# 2.net
KiCad netlist of a schematic drawn in Altium Designer
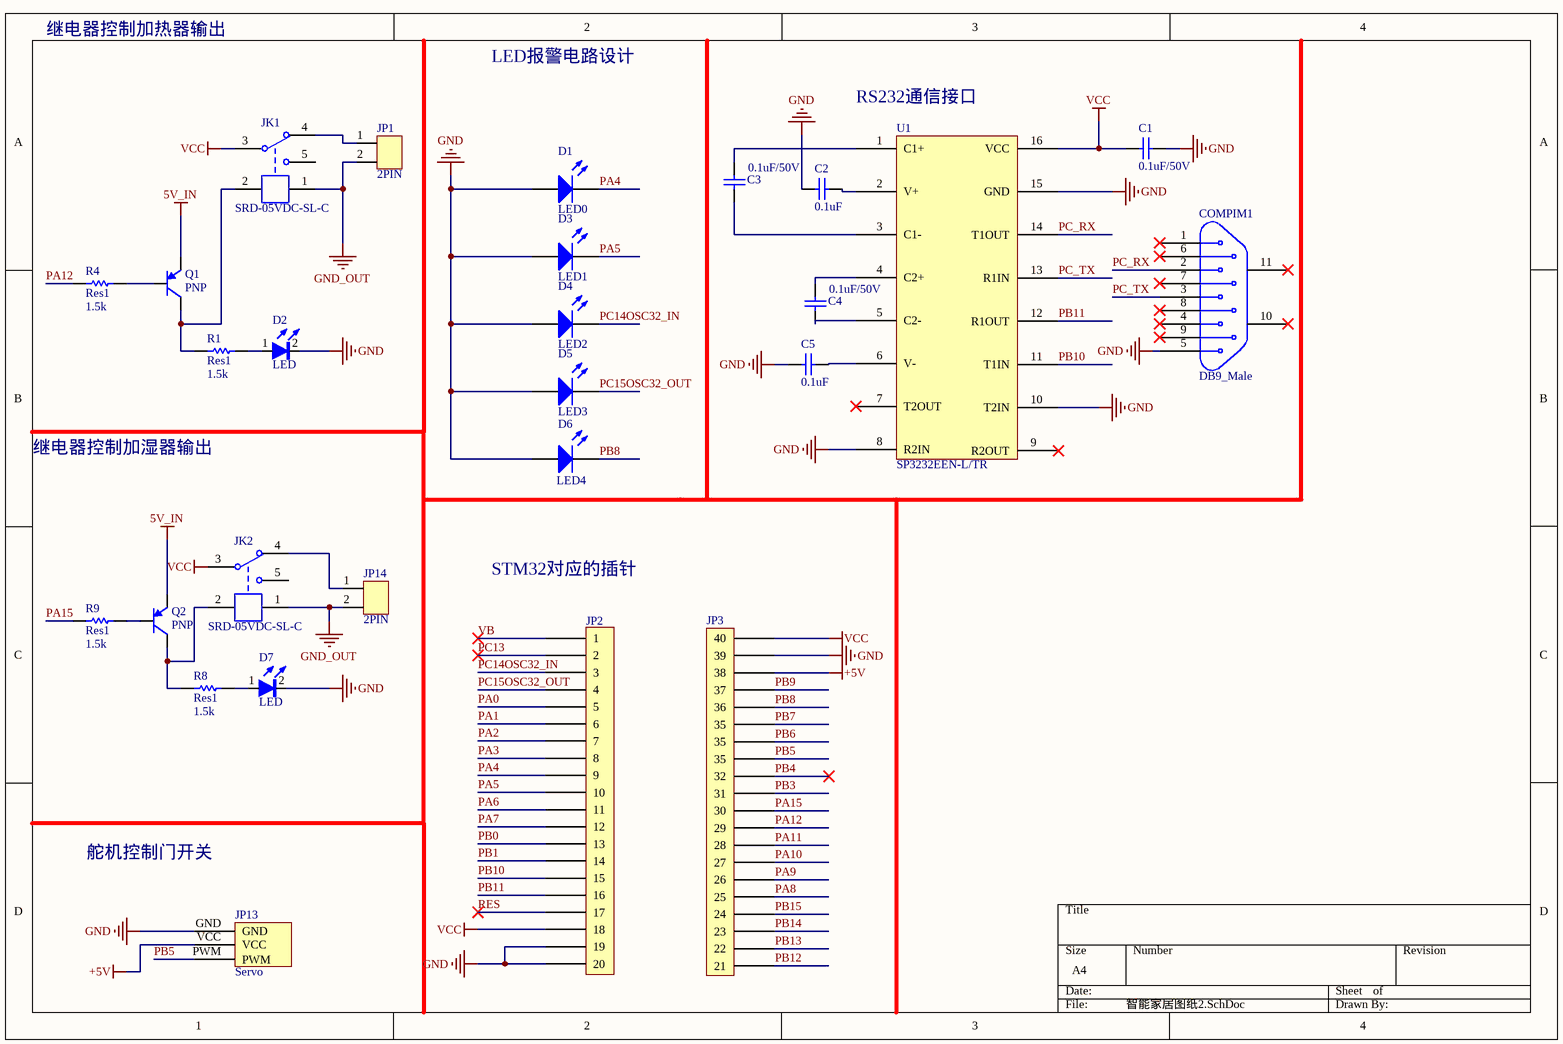
[diagram p0: 智能家居图纸2.SchDoc]

(export (version "E")
  (design (tool "Eeschema 10.0.6"))
  (components
    (comp (ref "C1")
      (value "0.1uF/50V")
      (footprint "C0603")
      (description "Capacitor")
      (fields (field (name "Comment") "Cap") (field (name "PUBLISHER") "Altium Limited"))
      (libsource (lib "Miscellaneous Devices") (part "Cap"))
    )
    (comp (ref "C2")
      (value "0.1uF")
      (footprint "C0603")
      (description "Capacitor")
      (fields (field (name "Comment") "Cap") (field (name "PUBLISHER") "Altium Limited"))
      (libsource (lib "Miscellaneous Devices") (part "Cap"))
    )
    (comp (ref "C3")
      (value "0.1uF/50V")
      (footprint "C0603")
      (description "Capacitor")
      (fields (field (name "Comment") "Cap") (field (name "PUBLISHER") "Altium Limited"))
      (libsource (lib "Miscellaneous Devices") (part "Cap"))
    )
    (comp (ref "C4")
      (value "0.1uF/50V")
      (footprint "C0603")
      (description "Capacitor")
      (fields (field (name "Comment") "Cap") (field (name "PUBLISHER") "Altium Limited"))
      (libsource (lib "Miscellaneous Devices") (part "Cap"))
    )
    (comp (ref "C5")
      (value "0.1uF")
      (footprint "C0603")
      (description "Capacitor")
      (fields (field (name "Comment") "Cap") (field (name "PUBLISHER") "Altium Limited"))
      (libsource (lib "Miscellaneous Devices") (part "Cap"))
    )
    (comp (ref "COMPIM1")
      (value "DB9_Male")
      (footprint "DB9Male")
      (description "9针串口线  RS232")
      (libsource (lib "智能家居") (part "DB9_Male"))
    )
    (comp (ref "D1")
      (value "LED0")
      (footprint "LED-Green")
      (description "Typical INFRARED GaAs LED")
      (fields (field (name "PUBLISHER") "Altium Limited"))
      (libsource (lib "Miscellaneous Devices") (part "LED0"))
    )
    (comp (ref "D2")
      (value "LED")
      (footprint "LED-Green")
      (description "发光二极管")
      (libsource (lib "智能家居") (part "LED"))
    )
    (comp (ref "D3")
      (value "LED1")
      (footprint "LED-Red")
      (description "Typical RED GaAs LED")
      (fields (field (name "PUBLISHER") "Altium Limited"))
      (libsource (lib "Miscellaneous Devices") (part "LED1"))
    )
    (comp (ref "D4")
      (value "LED2")
      (footprint "LED-White")
      (description "Typical RED, GREEN, YELLOW, AMBER GaAs LED")
      (fields (field (name "PUBLISHER") "Altium Limited"))
      (libsource (lib "Miscellaneous Devices") (part "LED2"))
    )
    (comp (ref "D5")
      (value "LED3")
      (footprint "LED-yellow")
      (description "Typical BLUE SiC LED")
      (fields (field (name "PUBLISHER") "Altium Limited"))
      (libsource (lib "Miscellaneous Devices") (part "LED3"))
    )
    (comp (ref "D6")
      (value "LED4")
      (footprint "LED-yellow")
      (description "发光二极管")
      (libsource (lib "0.3 - LED发光二极管") (part "LED"))
    )
    (comp (ref "D7")
      (value "LED")
      (footprint "LED-Red")
      (description "发光二极管")
      (libsource (lib "智能家居") (part "LED"))
    )
    (comp (ref "JK1")
      (value "SRD-05VDC-SL-C")
      (footprint "SRD-C_B")
      (description "5V一组转换")
      (fields (field (name "版权归属") "封装库来自淘宝卖家 ID：黄晶宝石"))
      (libsource (lib "1.5 - 继电器") (part "SRD-05VDC-SL-C"))
    )
    (comp (ref "JK2")
      (value "SRD-05VDC-SL-C")
      (footprint "SRD-C_B")
      (description "5V一组转换")
      (fields (field (name "版权归属") "封装库来自淘宝卖家 ID：黄晶宝石"))
      (libsource (lib "1.5 - 继电器") (part "SRD-05VDC-SL-C"))
    )
    (comp (ref "JP1")
      (value "2PIN")
      (footprint "2PIN")
      (description "插针")
      (libsource (lib "智能家居") (part "JP"))
    )
    (comp (ref "JP2")
      (value "JP3")
      (footprint "HDR1X20")
      (description "STM32插针第一列")
      (libsource (lib "智能家居") (part "JP3"))
    )
    (comp (ref "JP3")
      (value "JP4")
      (footprint "HDR1X20-2")
      (description "STM32插针第二列")
      (libsource (lib "智能家居") (part "JP4"))
    )
    (comp (ref "JP13")
      (value "Servo")
      (footprint "HDR1X3-5")
      (description "舵机")
      (libsource (lib "智能家居") (part "Servo"))
    )
    (comp (ref "JP14")
      (value "2PIN")
      (footprint "2PIN")
      (description "插针")
      (libsource (lib "智能家居") (part "JP"))
    )
    (comp (ref "Q1")
      (value "PNP")
      (footprint "PNP")
      (description "互补功率-PNP型")
      (fields (field (name "版权归属") "封装库来自淘宝 ID：黄晶宝石"))
      (libsource (lib "0.4 - 三极管") (part "45H11"))
    )
    (comp (ref "Q2")
      (value "PNP")
      (footprint "PNP")
      (description "互补功率-PNP型")
      (fields (field (name "版权归属") "封装库来自淘宝 ID：黄晶宝石"))
      (libsource (lib "0.4 - 三极管") (part "45H11"))
    )
    (comp (ref "R1")
      (value "Res1")
      (footprint "R200")
      (description "Resistor")
      (fields (field (name "ALTIUM_VALUE") "1.5k") (field (name "PUBLISHER") "Altium Limited"))
      (libsource (lib "Miscellaneous Devices") (part "Res1"))
    )
    (comp (ref "R4")
      (value "Res1")
      (footprint "R200")
      (description "Resistor")
      (fields (field (name "ALTIUM_VALUE") "1.5k") (field (name "PUBLISHER") "Altium Limited"))
      (libsource (lib "Miscellaneous Devices") (part "Res1"))
    )
    (comp (ref "R8")
      (value "Res1")
      (footprint "R200")
      (description "Resistor")
      (fields (field (name "ALTIUM_VALUE") "1.5k") (field (name "PUBLISHER") "Altium Limited"))
      (libsource (lib "Miscellaneous Devices") (part "Res1"))
    )
    (comp (ref "R9")
      (value "Res1")
      (footprint "R200")
      (description "Resistor")
      (fields (field (name "ALTIUM_VALUE") "1.5k") (field (name "PUBLISHER") "Altium Limited"))
      (libsource (lib "Miscellaneous Devices") (part "Res1"))
    )
    (comp (ref "U1")
      (value "SP3232EEN-L/TR")
      (footprint "SOP127P600X175-16N")
      (description "RS-232接口集成电路")
      (libsource (lib "智能家居") (part "SP3232EEN-L/TR"))
    )
  )
  (nets
    (net (code "1") (name "+5V") (class "Default")
      (node (ref "JP13") (pin "VCC") (pinfunction "VCC_VCC") (pintype "passive"))
      (node (ref "JP3") (pin "38") (pinfunction "38_38") (pintype "passive"))
    )
    (net (code "2") (name "/PA0") (class "Default")
      (node (ref "JP2") (pin "5") (pinfunction "5_5") (pintype "passive"))
    )
    (net (code "3") (name "/PA1") (class "Default")
      (node (ref "JP2") (pin "6") (pinfunction "6_6") (pintype "passive"))
    )
    (net (code "4") (name "/PA2") (class "Default")
      (node (ref "JP2") (pin "7") (pinfunction "7_7") (pintype "passive"))
    )
    (net (code "5") (name "/PA3") (class "Default")
      (node (ref "JP2") (pin "8") (pinfunction "8_8") (pintype "passive"))
    )
    (net (code "6") (name "/PA4") (class "Default")
      (node (ref "D1") (pin "2") (pinfunction "K_2") (pintype "passive"))
      (node (ref "JP2") (pin "9") (pinfunction "9_9") (pintype "passive"))
    )
    (net (code "7") (name "/PA5") (class "Default")
      (node (ref "D3") (pin "2") (pinfunction "K_2") (pintype "passive"))
      (node (ref "JP2") (pin "10") (pinfunction "10_10") (pintype "passive"))
    )
    (net (code "8") (name "/PA6") (class "Default")
      (node (ref "JP2") (pin "11") (pinfunction "11_11") (pintype "passive"))
    )
    (net (code "9") (name "/PA7") (class "Default")
      (node (ref "JP2") (pin "12") (pinfunction "12_12") (pintype "passive"))
    )
    (net (code "10") (name "/PA8") (class "Default")
      (node (ref "JP3") (pin "25") (pinfunction "25_25") (pintype "passive"))
    )
    (net (code "11") (name "/PA9") (class "Default")
      (node (ref "JP3") (pin "26") (pinfunction "26_26") (pintype "passive"))
    )
    (net (code "12") (name "/PA10") (class "Default")
      (node (ref "JP3") (pin "27") (pinfunction "27_27") (pintype "passive"))
    )
    (net (code "13") (name "/PA11") (class "Default")
      (node (ref "JP3") (pin "28") (pinfunction "28_28") (pintype "passive"))
    )
    (net (code "14") (name "/PA12") (class "Default")
      (node (ref "JP3") (pin "29") (pinfunction "29_29") (pintype "passive"))
      (node (ref "R4") (pin "2") (pinfunction "2_2") (pintype "passive"))
    )
    (net (code "15") (name "/PA15") (class "Default")
      (node (ref "JP3") (pin "30") (pinfunction "30_30") (pintype "passive"))
      (node (ref "R9") (pin "2") (pinfunction "2_2") (pintype "passive"))
    )
    (net (code "16") (name "/PB0") (class "Default")
      (node (ref "JP2") (pin "13") (pinfunction "13_13") (pintype "passive"))
    )
    (net (code "17") (name "/PB1") (class "Default")
      (node (ref "JP2") (pin "14") (pinfunction "14_14") (pintype "passive"))
    )
    (net (code "18") (name "/PB3") (class "Default")
      (node (ref "JP3") (pin "31") (pinfunction "31_31") (pintype "passive"))
    )
    (net (code "19") (name "/PB4") (class "Default")
      (node (ref "JP3") (pin "32") (pinfunction "32_32") (pintype "passive+no_connect"))
    )
    (net (code "20") (name "/PB5") (class "Default")
      (node (ref "JP13") (pin "PWM") (pinfunction "PWM_PWM") (pintype "passive"))
      (node (ref "JP3") (pin "33") (pinfunction "35_33") (pintype "passive"))
    )
    (net (code "21") (name "/PB6") (class "Default")
      (node (ref "JP3") (pin "34") (pinfunction "35_34") (pintype "passive"))
    )
    (net (code "22") (name "/PB7") (class "Default")
      (node (ref "JP3") (pin "35") (pinfunction "35_35") (pintype "passive"))
    )
    (net (code "23") (name "/PB8") (class "Default")
      (node (ref "D6") (pin "2") (pinfunction "K_2") (pintype "passive"))
      (node (ref "JP3") (pin "36") (pinfunction "36_36") (pintype "passive"))
    )
    (net (code "24") (name "/PB9") (class "Default")
      (node (ref "JP3") (pin "37") (pinfunction "37_37") (pintype "passive"))
    )
    (net (code "25") (name "/PB10") (class "Default")
      (node (ref "JP2") (pin "15") (pinfunction "15_15") (pintype "passive"))
      (node (ref "U1") (pin "11") (pinfunction "T1IN_11") (pintype "passive"))
    )
    (net (code "26") (name "/PB11") (class "Default")
      (node (ref "JP2") (pin "16") (pinfunction "16_16") (pintype "passive"))
      (node (ref "U1") (pin "12") (pinfunction "R1OUT_12") (pintype "passive"))
    )
    (net (code "27") (name "/PB12") (class "Default")
      (node (ref "JP3") (pin "21") (pinfunction "21_21") (pintype "passive"))
    )
    (net (code "28") (name "/PB13") (class "Default")
      (node (ref "JP3") (pin "22") (pinfunction "22_22") (pintype "passive"))
    )
    (net (code "29") (name "/PB14") (class "Default")
      (node (ref "JP3") (pin "23") (pinfunction "23_23") (pintype "passive"))
    )
    (net (code "30") (name "/PB15") (class "Default")
      (node (ref "JP3") (pin "24") (pinfunction "24_24") (pintype "passive"))
    )
    (net (code "31") (name "/PC13") (class "Default")
      (node (ref "JP2") (pin "2") (pinfunction "2_2") (pintype "passive+no_connect"))
    )
    (net (code "32") (name "/PC14OSC32_IN") (class "Default")
      (node (ref "D4") (pin "2") (pinfunction "K_2") (pintype "passive"))
      (node (ref "JP2") (pin "3") (pinfunction "3_3") (pintype "passive"))
    )
    (net (code "33") (name "/PC15OSC32_OUT") (class "Default")
      (node (ref "D5") (pin "2") (pinfunction "K_2") (pintype "passive"))
      (node (ref "JP2") (pin "4") (pinfunction "4_4") (pintype "passive"))
    )
    (net (code "34") (name "/PC_RX") (class "Default")
      (node (ref "COMPIM1") (pin "2") (pintype "passive"))
      (node (ref "U1") (pin "14") (pinfunction "T1OUT_14") (pintype "passive"))
    )
    (net (code "35") (name "/PC_TX") (class "Default")
      (node (ref "COMPIM1") (pin "3") (pintype "passive"))
      (node (ref "U1") (pin "13") (pinfunction "R1IN_13") (pintype "passive"))
    )
    (net (code "36") (name "/RES") (class "Default")
      (node (ref "JP2") (pin "17") (pinfunction "17_17") (pintype "passive+no_connect"))
    )
    (net (code "37") (name "/VB") (class "Default")
      (node (ref "JP2") (pin "1") (pinfunction "1_1") (pintype "passive+no_connect"))
    )
    (net (code "38") (name "5V_IN") (class "Default")
      (node (ref "Q1") (pin "3") (pinfunction "E_3") (pintype "passive"))
      (node (ref "Q2") (pin "3") (pinfunction "E_3") (pintype "passive"))
    )
    (net (code "39") (name "GND") (class "Default")
      (node (ref "C1") (pin "1") (pinfunction "1_1") (pintype "passive"))
      (node (ref "C2") (pin "1") (pinfunction "1_1") (pintype "passive"))
      (node (ref "C5") (pin "1") (pinfunction "1_1") (pintype "passive"))
      (node (ref "COMPIM1") (pin "5") (pintype "passive"))
      (node (ref "D1") (pin "1") (pinfunction "A_1") (pintype "passive"))
      (node (ref "D2") (pin "2") (pinfunction "2_2") (pintype "passive"))
      (node (ref "D3") (pin "1") (pinfunction "A_1") (pintype "passive"))
      (node (ref "D4") (pin "1") (pinfunction "A_1") (pintype "passive"))
      (node (ref "D5") (pin "1") (pinfunction "A_1") (pintype "passive"))
      (node (ref "D6") (pin "1") (pinfunction "A_1") (pintype "passive"))
      (node (ref "D7") (pin "2") (pinfunction "2_2") (pintype "passive"))
      (node (ref "JP13") (pin "GND") (pinfunction "GND_GND") (pintype "passive"))
      (node (ref "JP2") (pin "19") (pinfunction "19_19") (pintype "passive"))
      (node (ref "JP2") (pin "20") (pinfunction "20_20") (pintype "passive"))
      (node (ref "JP3") (pin "39") (pinfunction "39_39") (pintype "passive"))
      (node (ref "U1") (pin "10") (pinfunction "T2IN_10") (pintype "passive"))
      (node (ref "U1") (pin "15") (pinfunction "GND_15") (pintype "passive"))
      (node (ref "U1") (pin "8") (pinfunction "R2IN_8") (pintype "passive"))
    )
    (net (code "40") (name "GND_OUT") (class "Default")
      (node (ref "JK1") (pin "1") (pinfunction "1_1") (pintype "passive"))
      (node (ref "JK2") (pin "1") (pinfunction "1_1") (pintype "passive"))
      (node (ref "JP1") (pin "2") (pintype "passive"))
      (node (ref "JP14") (pin "2") (pintype "passive"))
    )
    (net (code "41") (name "Net-(D2-Pad1)") (class "Default")
      (node (ref "D2") (pin "1") (pinfunction "1_1") (pintype "passive"))
      (node (ref "R1") (pin "2") (pinfunction "2_2") (pintype "passive"))
    )
    (net (code "42") (name "Net-(D7-Pad1)") (class "Default")
      (node (ref "D7") (pin "1") (pinfunction "1_1") (pintype "passive"))
      (node (ref "R8") (pin "2") (pinfunction "2_2") (pintype "passive"))
    )
    (net (code "43") (name "Net-(JK1-Pad4)") (class "Default")
      (node (ref "JK1") (pin "4") (pinfunction "4_4") (pintype "passive"))
      (node (ref "JP1") (pin "1") (pintype "passive"))
    )
    (net (code "44") (name "Net-(JK2-Pad4)") (class "Default")
      (node (ref "JK2") (pin "4") (pinfunction "4_4") (pintype "passive"))
      (node (ref "JP14") (pin "1") (pintype "passive"))
    )
    (net (code "45") (name "Net-(Q1-B)") (class "Default")
      (node (ref "Q1") (pin "1") (pinfunction "B_1") (pintype "passive"))
      (node (ref "R4") (pin "1") (pinfunction "1_1") (pintype "passive"))
    )
    (net (code "46") (name "Net-(Q1-C)") (class "Default")
      (node (ref "JK1") (pin "2") (pinfunction "2_2") (pintype "passive"))
      (node (ref "Q1") (pin "2") (pinfunction "C_2") (pintype "passive"))
      (node (ref "R1") (pin "1") (pinfunction "1_1") (pintype "passive"))
    )
    (net (code "47") (name "Net-(Q2-B)") (class "Default")
      (node (ref "Q2") (pin "1") (pinfunction "B_1") (pintype "passive"))
      (node (ref "R9") (pin "1") (pinfunction "1_1") (pintype "passive"))
    )
    (net (code "48") (name "Net-(Q2-C)") (class "Default")
      (node (ref "JK2") (pin "2") (pinfunction "2_2") (pintype "passive"))
      (node (ref "Q2") (pin "2") (pinfunction "C_2") (pintype "passive"))
      (node (ref "R8") (pin "1") (pinfunction "1_1") (pintype "passive"))
    )
    (net (code "49") (name "Net-(U1-C1+)") (class "Default")
      (node (ref "C3") (pin "2") (pinfunction "2_2") (pintype "passive"))
      (node (ref "U1") (pin "1") (pinfunction "C1+_1") (pintype "passive"))
    )
    (net (code "50") (name "Net-(U1-C1-)") (class "Default")
      (node (ref "C3") (pin "1") (pinfunction "1_1") (pintype "passive"))
      (node (ref "U1") (pin "3") (pinfunction "C1-_3") (pintype "passive"))
    )
    (net (code "51") (name "Net-(U1-C2+)") (class "Default")
      (node (ref "C4") (pin "2") (pinfunction "2_2") (pintype "passive"))
      (node (ref "U1") (pin "4") (pinfunction "C2+_4") (pintype "passive"))
    )
    (net (code "52") (name "Net-(U1-C2-)") (class "Default")
      (node (ref "C4") (pin "1") (pinfunction "1_1") (pintype "passive"))
      (node (ref "U1") (pin "5") (pinfunction "C2-_5") (pintype "passive"))
    )
    (net (code "53") (name "Net-(U1-V+)") (class "Default")
      (node (ref "C2") (pin "2") (pinfunction "2_2") (pintype "passive"))
      (node (ref "U1") (pin "2") (pinfunction "V+_2") (pintype "passive"))
    )
    (net (code "54") (name "Net-(U1-V-)") (class "Default")
      (node (ref "C5") (pin "2") (pinfunction "2_2") (pintype "passive"))
      (node (ref "U1") (pin "6") (pinfunction "V-_6") (pintype "passive"))
    )
    (net (code "55") (name "VCC") (class "Default")
      (node (ref "C1") (pin "2") (pinfunction "2_2") (pintype "passive"))
      (node (ref "JK1") (pin "3") (pinfunction "3_3") (pintype "passive"))
      (node (ref "JK2") (pin "3") (pinfunction "3_3") (pintype "passive"))
      (node (ref "JP2") (pin "18") (pinfunction "18_18") (pintype "passive"))
      (node (ref "JP3") (pin "40") (pinfunction "40_40") (pintype "passive"))
      (node (ref "U1") (pin "16") (pinfunction "VCC_16") (pintype "passive"))
    )
    (net (code "56") (name "unconnected-(COMPIM1-Pad1)") (class "Default")
      (node (ref "COMPIM1") (pin "1") (pintype "passive+no_connect"))
    )
    (net (code "57") (name "unconnected-(COMPIM1-Pad4)") (class "Default")
      (node (ref "COMPIM1") (pin "4") (pintype "passive+no_connect"))
    )
    (net (code "58") (name "unconnected-(COMPIM1-Pad6)") (class "Default")
      (node (ref "COMPIM1") (pin "6") (pintype "passive+no_connect"))
    )
    (net (code "59") (name "unconnected-(COMPIM1-Pad7)") (class "Default")
      (node (ref "COMPIM1") (pin "7") (pintype "passive+no_connect"))
    )
    (net (code "60") (name "unconnected-(COMPIM1-Pad8)") (class "Default")
      (node (ref "COMPIM1") (pin "8") (pintype "passive+no_connect"))
    )
    (net (code "61") (name "unconnected-(COMPIM1-Pad9)") (class "Default")
      (node (ref "COMPIM1") (pin "9") (pintype "passive+no_connect"))
    )
    (net (code "62") (name "unconnected-(COMPIM1-Pad10)") (class "Default")
      (node (ref "COMPIM1") (pin "10") (pintype "passive+no_connect"))
    )
    (net (code "63") (name "unconnected-(COMPIM1-Pad11)") (class "Default")
      (node (ref "COMPIM1") (pin "11") (pintype "passive+no_connect"))
    )
    (net (code "64") (name "unconnected-(JK1-Pad5)") (class "Default")
      (node (ref "JK1") (pin "5") (pinfunction "5_5") (pintype "passive"))
    )
    (net (code "65") (name "unconnected-(JK2-Pad5)") (class "Default")
      (node (ref "JK2") (pin "5") (pinfunction "5_5") (pintype "passive"))
    )
    (net (code "66") (name "unconnected-(U1-R2OUT-Pad9)") (class "Default")
      (node (ref "U1") (pin "9") (pinfunction "R2OUT_9") (pintype "passive+no_connect"))
    )
    (net (code "67") (name "unconnected-(U1-T2OUT-Pad7)") (class "Default")
      (node (ref "U1") (pin "7") (pinfunction "T2OUT_7") (pintype "passive+no_connect"))
    )
  )
)
